# E1706R_Schematic.net
KiCad netlist of a schematic drawn in Altium Designer
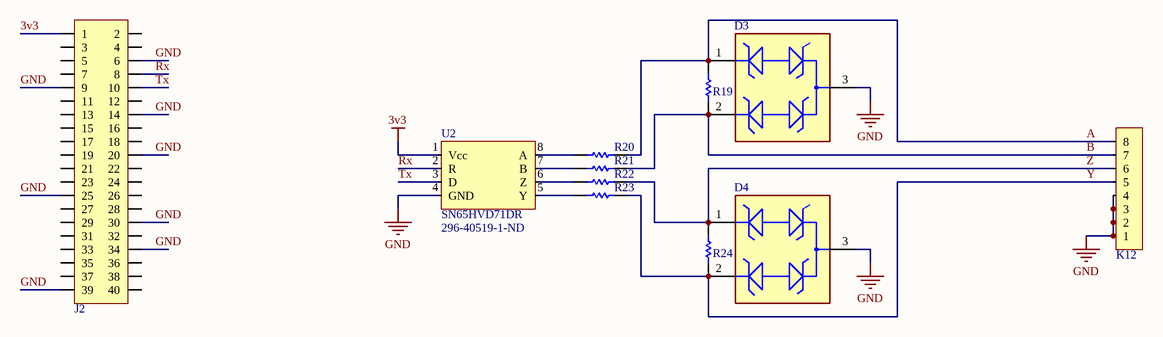
[diagram p0: E1706R_Schematic.SchDoc]

(export (version "E")
  (design (tool "Eeschema 10.0.6"))
  (components
    (comp (ref "D3")
      (value "CDSOT23-SM712")
      (footprint "FP-SOT23-MFG")
      (description "TVS DIODE 7V/12V 14V/26V SOT23-3")
      (fields
        (field (name "MANUFACTURER") "Bourns Inc.")
        (field (name "OCTOPART") "https://octopart.com/cdsot23-sm712-bourns-7576327")
      )
      (libsource (lib "Altium Content Vault") (part "81303f94231262926866863442dad16"))
    )
    (comp (ref "D4")
      (value "CDSOT23-SM712")
      (footprint "FP-SOT23-MFG")
      (description "TVS DIODE 7V/12V 14V/26V SOT23-3")
      (fields
        (field (name "MANUFACTURER") "Bourns Inc.")
        (field (name "OCTOPART") "https://octopart.com/cdsot23-sm712-bourns-7576327")
      )
      (libsource (lib "Altium Content Vault") (part "81303f94231262926866863442dad16"))
    )
    (comp (ref "J2")
      (value "2223")
      (footprint "2223")
      (description "40 PIN 20X2 CONN")
      (libsource (lib "SchLibrary") (part "2223"))
    )
    (comp (ref "K12")
      (value "6339191-5")
      (footprint "6339191-5")
      (libsource (lib "SchLibrary") (part "6339191-5"))
    )
    (comp (ref "R19")
      (value "Res_120_0805")
      (footprint "RESC2012N")
      (description "RES 120 OHM 1/8W 1% 0805")
      (libsource (lib "Erico_Ignitor") (part "Res_120_0805"))
    )
    (comp (ref "R20")
      (value "Res_10_0805")
      (footprint "RESC2012N")
      (description "RES 10 OHM 1/8W 1% 0805")
      (fields (field (name "MANUFACTURER") "Vishay Dale") (field (name "TOLERANCE") "±1%"))
      (libsource (lib "Erico_Ignitor") (part "Res_10_0805"))
    )
    (comp (ref "R21")
      (value "Res_10_0805")
      (footprint "RESC2012N")
      (description "RES 10 OHM 1/8W 1% 0805")
      (fields (field (name "MANUFACTURER") "Vishay Dale") (field (name "TOLERANCE") "±1%"))
      (libsource (lib "Erico_Ignitor") (part "Res_10_0805"))
    )
    (comp (ref "R22")
      (value "Res_10_0805")
      (footprint "RESC2012N")
      (description "RES 10 OHM 1/8W 1% 0805")
      (fields (field (name "MANUFACTURER") "Vishay Dale") (field (name "TOLERANCE") "±1%"))
      (libsource (lib "Erico_Ignitor") (part "Res_10_0805"))
    )
    (comp (ref "R23")
      (value "Res_10_0805")
      (footprint "RESC2012N")
      (description "RES 10 OHM 1/8W 1% 0805")
      (fields (field (name "MANUFACTURER") "Vishay Dale") (field (name "TOLERANCE") "±1%"))
      (libsource (lib "Erico_Ignitor") (part "Res_10_0805"))
    )
    (comp (ref "R24")
      (value "Res_120_0805")
      (footprint "RESC2012N")
      (description "RES 120 OHM 1/8W 1% 0805")
      (libsource (lib "Erico_Ignitor") (part "Res_120_0805"))
    )
    (comp (ref "U2")
      (value "SN65HVD71DR")
      (footprint "SN65HVD71DR")
      (description "Single Transmitter/Receiver RS-485 8-Pin SOIC T/R")
      (fields
        (field (name "SUPPLIER PART NUMBER 1") "296-40519-1-ND")
        (field (name "MANUFACTURER") "Texas Instruments")
      )
      (libsource (lib "SchLibrary") (part "SN65HVD71DR"))
    )
  )
  (nets
    (net (code "1") (name "/A") (class "Default")
      (node (ref "D3") (pin "1") (pinfunction "1_1") (pintype "passive"))
      (node (ref "K12") (pin "8") (pinfunction "8_8") (pintype "passive"))
      (node (ref "R19") (pin "2") (pinfunction "2_2") (pintype "passive"))
      (node (ref "R20") (pin "2") (pinfunction "2_2") (pintype "passive"))
    )
    (net (code "2") (name "/B") (class "Default")
      (node (ref "D3") (pin "2") (pinfunction "2_2") (pintype "passive"))
      (node (ref "K12") (pin "7") (pinfunction "7_7") (pintype "passive"))
      (node (ref "R19") (pin "1") (pinfunction "1_1") (pintype "passive"))
      (node (ref "R21") (pin "2") (pinfunction "2_2") (pintype "passive"))
    )
    (net (code "3") (name "/Rx") (class "Default")
      (node (ref "J2") (pin "8") (pinfunction "8_8") (pintype "passive"))
      (node (ref "U2") (pin "2") (pinfunction "R_2") (pintype "passive"))
    )
    (net (code "4") (name "/Tx") (class "Default")
      (node (ref "J2") (pin "10") (pinfunction "10_10") (pintype "passive"))
      (node (ref "U2") (pin "3") (pinfunction "D_3") (pintype "passive"))
    )
    (net (code "5") (name "/Y") (class "Default")
      (node (ref "D4") (pin "2") (pinfunction "2_2") (pintype "passive"))
      (node (ref "K12") (pin "5") (pinfunction "5_5") (pintype "passive"))
      (node (ref "R23") (pin "2") (pinfunction "2_2") (pintype "passive"))
      (node (ref "R24") (pin "1") (pinfunction "1_1") (pintype "passive"))
    )
    (net (code "6") (name "/Z") (class "Default")
      (node (ref "D4") (pin "1") (pinfunction "1_1") (pintype "passive"))
      (node (ref "K12") (pin "6") (pinfunction "6_6") (pintype "passive"))
      (node (ref "R22") (pin "2") (pinfunction "2_2") (pintype "passive"))
      (node (ref "R24") (pin "2") (pinfunction "2_2") (pintype "passive"))
    )
    (net (code "7") (name "3v3") (class "Default")
      (node (ref "J2") (pin "1") (pinfunction "1_1") (pintype "passive"))
      (node (ref "U2") (pin "1") (pinfunction "Vcc_1") (pintype "passive"))
    )
    (net (code "8") (name "GND") (class "Default")
      (node (ref "D3") (pin "3") (pinfunction "3_3") (pintype "passive"))
      (node (ref "D4") (pin "3") (pinfunction "3_3") (pintype "passive"))
      (node (ref "J2") (pin "14") (pinfunction "14_14") (pintype "passive"))
      (node (ref "J2") (pin "20") (pinfunction "20_20") (pintype "passive"))
      (node (ref "J2") (pin "25") (pinfunction "25_25") (pintype "passive"))
      (node (ref "J2") (pin "30") (pinfunction "30_30") (pintype "passive"))
      (node (ref "J2") (pin "34") (pinfunction "34_34") (pintype "passive"))
      (node (ref "J2") (pin "39") (pinfunction "39_39") (pintype "passive"))
      (node (ref "J2") (pin "6") (pinfunction "6_6") (pintype "passive"))
      (node (ref "J2") (pin "9") (pinfunction "9_9") (pintype "passive"))
      (node (ref "K12") (pin "1") (pinfunction "1_1") (pintype "passive"))
      (node (ref "K12") (pin "2") (pinfunction "2_2") (pintype "passive"))
      (node (ref "K12") (pin "3") (pinfunction "3_3") (pintype "passive"))
      (node (ref "K12") (pin "4") (pinfunction "4_4") (pintype "passive"))
      (node (ref "U2") (pin "4") (pinfunction "GND_4") (pintype "passive"))
    )
    (net (code "9") (name "Net-(U2-A)") (class "Default")
      (node (ref "R20") (pin "1") (pinfunction "1_1") (pintype "passive"))
      (node (ref "U2") (pin "8") (pinfunction "A_8") (pintype "passive"))
    )
    (net (code "10") (name "Net-(U2-B)") (class "Default")
      (node (ref "R21") (pin "1") (pinfunction "1_1") (pintype "passive"))
      (node (ref "U2") (pin "7") (pinfunction "B_7") (pintype "passive"))
    )
    (net (code "11") (name "Net-(U2-Y)") (class "Default")
      (node (ref "R23") (pin "1") (pinfunction "1_1") (pintype "passive"))
      (node (ref "U2") (pin "5") (pinfunction "Y_5") (pintype "passive"))
    )
    (net (code "12") (name "Net-(U2-Z)") (class "Default")
      (node (ref "R22") (pin "1") (pinfunction "1_1") (pintype "passive"))
      (node (ref "U2") (pin "6") (pinfunction "Z_6") (pintype "passive"))
    )
    (net (code "13") (name "unconnected-(J2-Pad2)") (class "Default")
      (node (ref "J2") (pin "2") (pinfunction "2_2") (pintype "passive"))
    )
    (net (code "14") (name "unconnected-(J2-Pad3)") (class "Default")
      (node (ref "J2") (pin "3") (pinfunction "3_3") (pintype "passive"))
    )
    (net (code "15") (name "unconnected-(J2-Pad4)") (class "Default")
      (node (ref "J2") (pin "4") (pinfunction "4_4") (pintype "passive"))
    )
    (net (code "16") (name "unconnected-(J2-Pad5)") (class "Default")
      (node (ref "J2") (pin "5") (pinfunction "5_5") (pintype "passive"))
    )
    (net (code "17") (name "unconnected-(J2-Pad7)") (class "Default")
      (node (ref "J2") (pin "7") (pinfunction "7_7") (pintype "passive"))
    )
    (net (code "18") (name "unconnected-(J2-Pad11)") (class "Default")
      (node (ref "J2") (pin "11") (pinfunction "11_11") (pintype "passive"))
    )
    (net (code "19") (name "unconnected-(J2-Pad12)") (class "Default")
      (node (ref "J2") (pin "12") (pinfunction "12_12") (pintype "passive"))
    )
    (net (code "20") (name "unconnected-(J2-Pad13)") (class "Default")
      (node (ref "J2") (pin "13") (pinfunction "13_13") (pintype "passive"))
    )
    (net (code "21") (name "unconnected-(J2-Pad15)") (class "Default")
      (node (ref "J2") (pin "15") (pinfunction "15_15") (pintype "passive"))
    )
    (net (code "22") (name "unconnected-(J2-Pad16)") (class "Default")
      (node (ref "J2") (pin "16") (pinfunction "16_16") (pintype "passive"))
    )
    (net (code "23") (name "unconnected-(J2-Pad17)") (class "Default")
      (node (ref "J2") (pin "17") (pinfunction "17_17") (pintype "passive"))
    )
    (net (code "24") (name "unconnected-(J2-Pad18)") (class "Default")
      (node (ref "J2") (pin "18") (pinfunction "18_18") (pintype "passive"))
    )
    (net (code "25") (name "unconnected-(J2-Pad19)") (class "Default")
      (node (ref "J2") (pin "19") (pinfunction "19_19") (pintype "passive"))
    )
    (net (code "26") (name "unconnected-(J2-Pad21)") (class "Default")
      (node (ref "J2") (pin "21") (pinfunction "21_21") (pintype "passive"))
    )
    (net (code "27") (name "unconnected-(J2-Pad22)") (class "Default")
      (node (ref "J2") (pin "22") (pinfunction "22_22") (pintype "passive"))
    )
    (net (code "28") (name "unconnected-(J2-Pad23)") (class "Default")
      (node (ref "J2") (pin "23") (pinfunction "23_23") (pintype "passive"))
    )
    (net (code "29") (name "unconnected-(J2-Pad24)") (class "Default")
      (node (ref "J2") (pin "24") (pinfunction "24_24") (pintype "passive"))
    )
    (net (code "30") (name "unconnected-(J2-Pad26)") (class "Default")
      (node (ref "J2") (pin "26") (pinfunction "26_26") (pintype "passive"))
    )
    (net (code "31") (name "unconnected-(J2-Pad27)") (class "Default")
      (node (ref "J2") (pin "27") (pinfunction "27_27") (pintype "passive"))
    )
    (net (code "32") (name "unconnected-(J2-Pad28)") (class "Default")
      (node (ref "J2") (pin "28") (pinfunction "28_28") (pintype "passive"))
    )
    (net (code "33") (name "unconnected-(J2-Pad29)") (class "Default")
      (node (ref "J2") (pin "29") (pinfunction "29_29") (pintype "passive"))
    )
    (net (code "34") (name "unconnected-(J2-Pad31)") (class "Default")
      (node (ref "J2") (pin "31") (pinfunction "31_31") (pintype "passive"))
    )
    (net (code "35") (name "unconnected-(J2-Pad32)") (class "Default")
      (node (ref "J2") (pin "32") (pinfunction "32_32") (pintype "passive"))
    )
    (net (code "36") (name "unconnected-(J2-Pad33)") (class "Default")
      (node (ref "J2") (pin "33") (pinfunction "33_33") (pintype "passive"))
    )
    (net (code "37") (name "unconnected-(J2-Pad35)") (class "Default")
      (node (ref "J2") (pin "35") (pinfunction "35_35") (pintype "passive"))
    )
    (net (code "38") (name "unconnected-(J2-Pad36)") (class "Default")
      (node (ref "J2") (pin "36") (pinfunction "36_36") (pintype "passive"))
    )
    (net (code "39") (name "unconnected-(J2-Pad37)") (class "Default")
      (node (ref "J2") (pin "37") (pinfunction "37_37") (pintype "passive"))
    )
    (net (code "40") (name "unconnected-(J2-Pad38)") (class "Default")
      (node (ref "J2") (pin "38") (pinfunction "38_38") (pintype "passive"))
    )
    (net (code "41") (name "unconnected-(J2-Pad40)") (class "Default")
      (node (ref "J2") (pin "40") (pinfunction "40_40") (pintype "passive"))
    )
  )
)
